# LVDS_IFC.net
KiCad netlist of a schematic drawn in Altium Designer
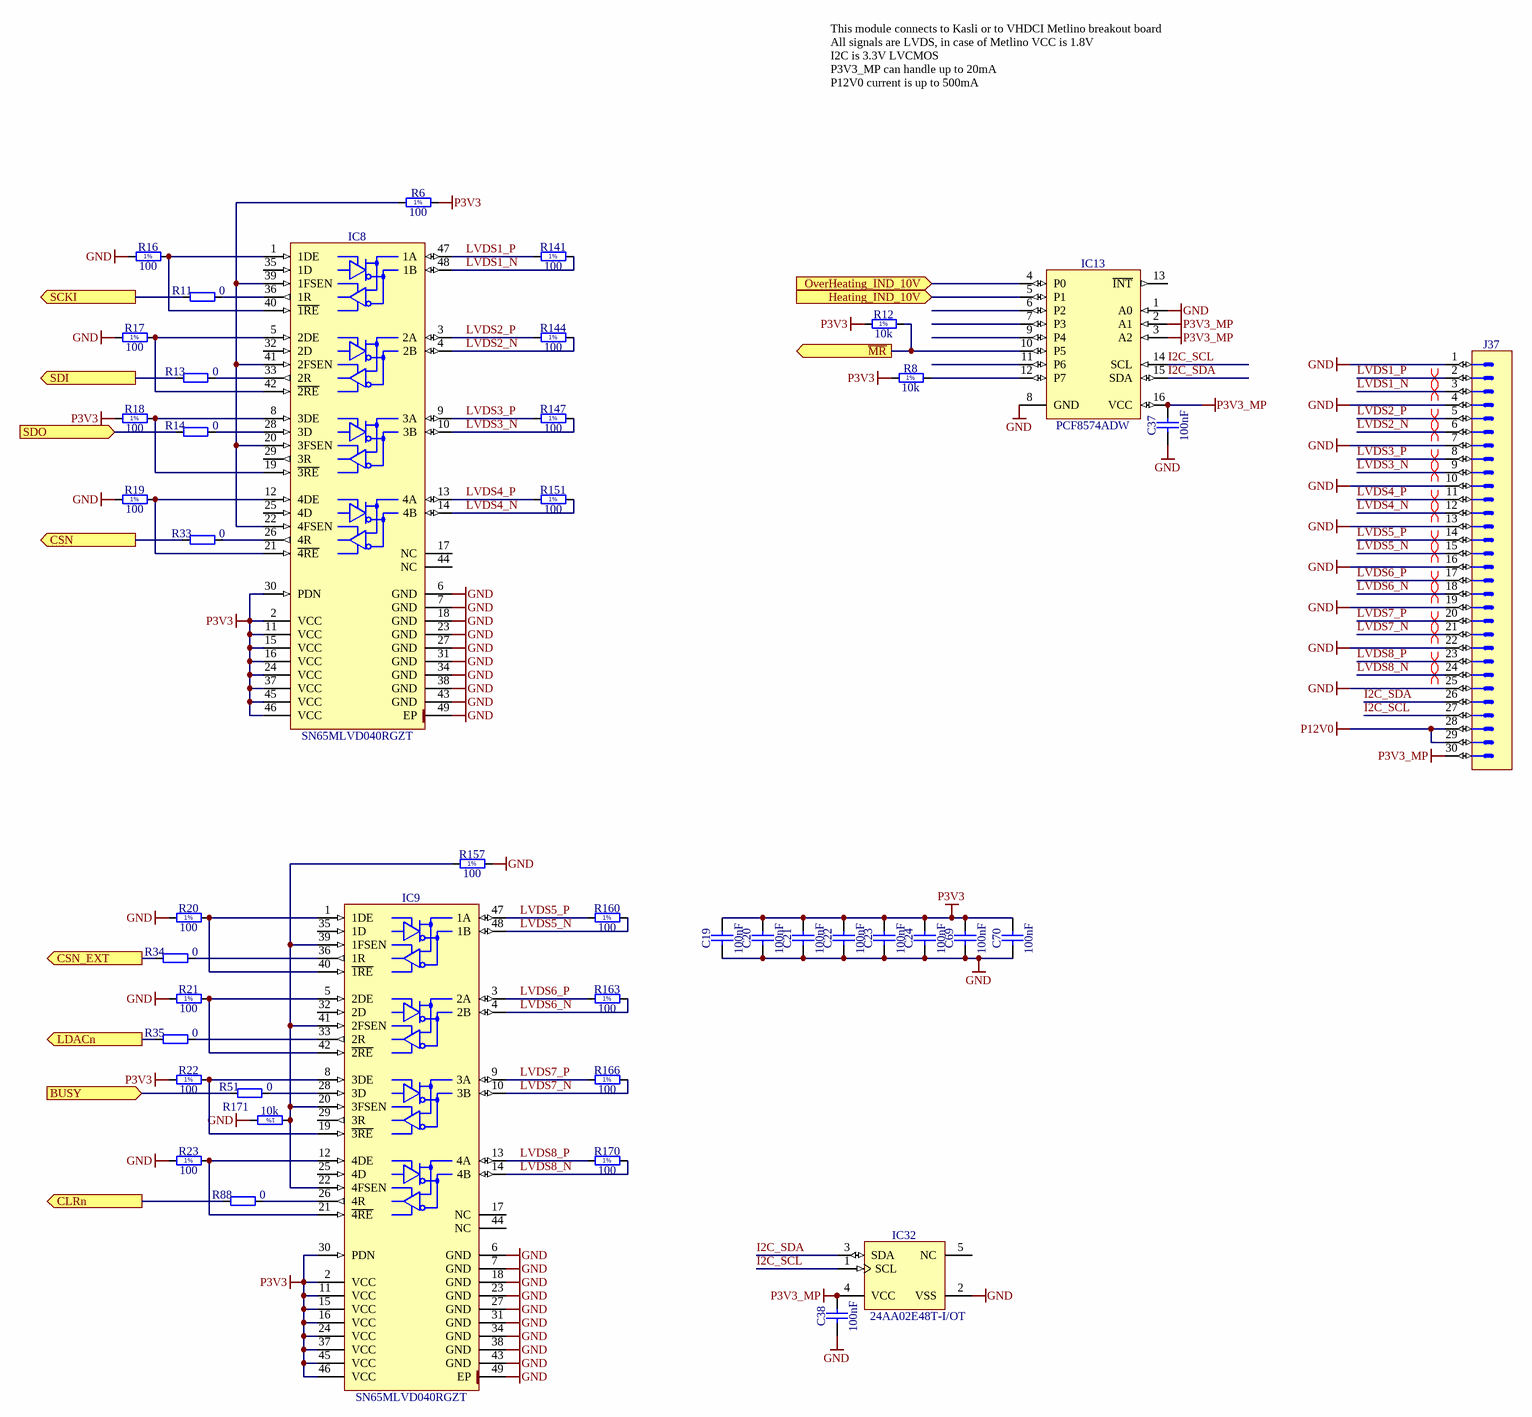
[diagram p0: LVDS_IFC.SchDoc]

(export (version "E")
  (design (tool "Eeschema 10.0.6"))
  (components
    (comp (ref "C19")
      (value "100nF")
      (footprint "CAPC1005X55N")
      (description "Non-polarised capacitor")
      (fields
        (field (name "PART NUMBER") "CC0402_100NF_16V_10%_X5R")
        (field (name "VOLTAGE") "16V")
        (field (name "AUTHOR") "CERN DEM JLC")
      )
      (libsource (lib "Capacitors") (part "Capacitor - non polarized"))
    )
    (comp (ref "C20")
      (value "100nF")
      (footprint "CAPC1005X55N")
      (description "Non-polarised capacitor")
      (fields
        (field (name "PART NUMBER") "CC0402_100NF_16V_10%_X5R")
        (field (name "VOLTAGE") "16V")
        (field (name "AUTHOR") "CERN DEM JLC")
      )
      (libsource (lib "Capacitors") (part "Capacitor - non polarized"))
    )
    (comp (ref "C21")
      (value "100nF")
      (footprint "CAPC1005X55N")
      (description "Non-polarised capacitor")
      (fields
        (field (name "PART NUMBER") "CC0402_100NF_16V_10%_X5R")
        (field (name "VOLTAGE") "16V")
        (field (name "AUTHOR") "CERN DEM JLC")
      )
      (libsource (lib "Capacitors") (part "Capacitor - non polarized"))
    )
    (comp (ref "C22")
      (value "100nF")
      (footprint "CAPC1005X55N")
      (description "Non-polarised capacitor")
      (fields
        (field (name "PART NUMBER") "CC0402_100NF_16V_10%_X5R")
        (field (name "VOLTAGE") "16V")
        (field (name "AUTHOR") "CERN DEM JLC")
      )
      (libsource (lib "Capacitors") (part "Capacitor - non polarized"))
    )
    (comp (ref "C23")
      (value "100nF")
      (footprint "CAPC1005X55N")
      (description "Non-polarised capacitor")
      (fields
        (field (name "PART NUMBER") "CC0402_100NF_16V_10%_X5R")
        (field (name "VOLTAGE") "16V")
        (field (name "AUTHOR") "CERN DEM JLC")
      )
      (libsource (lib "Capacitors") (part "Capacitor - non polarized"))
    )
    (comp (ref "C24")
      (value "100nF")
      (footprint "CAPC1005X55N")
      (description "Non-polarised capacitor")
      (fields
        (field (name "PART NUMBER") "CC0402_100NF_16V_10%_X5R")
        (field (name "VOLTAGE") "16V")
        (field (name "AUTHOR") "CERN DEM JLC")
      )
      (libsource (lib "Capacitors") (part "Capacitor - non polarized"))
    )
    (comp (ref "C37")
      (value "100nF")
      (footprint "CAPC1005X55N")
      (description "Non-polarised capacitor")
      (fields
        (field (name "PART NUMBER") "CC0402_100NF_16V_10%_X5R")
        (field (name "VOLTAGE") "16V")
        (field (name "AUTHOR") "CERN DEM JLC")
      )
      (libsource (lib "Capacitors") (part "Capacitor - non polarized"))
    )
    (comp (ref "C38")
      (value "100nF")
      (footprint "CAPC1005X55N")
      (description "Non-polarised capacitor")
      (fields
        (field (name "PART NUMBER") "CC0402_100NF_16V_10%_X5R")
        (field (name "VOLTAGE") "16V")
        (field (name "AUTHOR") "CERN DEM JLC")
      )
      (libsource (lib "Capacitors") (part "Capacitor - non polarized"))
    )
    (comp (ref "C69")
      (value "100nF")
      (footprint "CAPC1005X55N")
      (description "Non-polarised capacitor")
      (fields
        (field (name "PART NUMBER") "CC0402_100NF_16V_10%_X5R")
        (field (name "VOLTAGE") "16V")
        (field (name "AUTHOR") "CERN DEM JLC")
      )
      (libsource (lib "Capacitors") (part "Capacitor - non polarized"))
    )
    (comp (ref "C70")
      (value "100nF")
      (footprint "CAPC1005X55N")
      (description "Non-polarised capacitor")
      (fields
        (field (name "PART NUMBER") "CC0402_100NF_16V_10%_X5R")
        (field (name "VOLTAGE") "16V")
        (field (name "AUTHOR") "CERN DEM JLC")
      )
      (libsource (lib "Capacitors") (part "Capacitor - non polarized"))
    )
    (comp (ref "IC8")
      (value "SN65MLVD040RGZT")
      (footprint "QFN50P700X700X100-49N-S420")
      (description "4-Channel Half-Duplex M-LVDS Line Transceiver")
      (fields (field (name "MANUFACTURER") "TEXAS INSTRUMENTS") (field (name "AUTHOR") "CERN DEM JLC"))
      (libsource (lib "ICs And Semiconductors") (part "SN65MLVD040"))
    )
    (comp (ref "IC9")
      (value "SN65MLVD040RGZT")
      (footprint "QFN50P700X700X100-49N-S420")
      (description "4-Channel Half-Duplex M-LVDS Line Transceiver")
      (fields (field (name "MANUFACTURER") "TEXAS INSTRUMENTS") (field (name "AUTHOR") "CERN DEM JLC"))
      (libsource (lib "ICs And Semiconductors") (part "SN65MLVD040"))
    )
    (comp (ref "IC13")
      (value "PCF8574ADW")
      (footprint "SOIC127P1030X265-16N")
      (description "Remote 8-bit I/O Expander For I2C Bus")
      (fields (field (name "MANUFACTURER") "TEXAS INSTRUMENTS") (field (name "AUTHOR") "CERN DEM JLC"))
      (libsource (lib "ICs And Semiconductors") (part "PCF8574ADW"))
    )
    (comp (ref "IC32")
      (value "24AA02E48T-I/OT")
      (footprint "SOT95P280X145-5N")
      (description "1.7V-5.5V, 2K I2C Serial EEPROM With EUI-48 Node Identity")
      (fields (field (name "MANUFACTURER") "MICROCHIP TECHNOLOGY") (field (name "AUTHOR") "CERN DEM MR"))
      (libsource (lib "ICs And Semiconductors") (part "24AA02E48T-I/OT"))
    )
    (comp (ref "J37")
      (value "~")
      (footprint "3M_N2530-6002RB")
      (description "Connector 30 Male")
      (fields
        (field (name "PART NUMBER") "3M_N2530-6002RB")
        (field (name "MANUFACTURER") "3M")
        (field (name "AUTHOR") "CERN DEM JLC")
      )
      (libsource (lib "Connectors") (part "Connector 30 Male"))
    )
    (comp (ref "R6")
      (value "100")
      (footprint "RESC1005X40N")
      (description "Resistor - 1%")
      (fields
        (field (name "PART NUMBER") "R0402_100R_1%_0.1W_100PPM")
        (field (name "POWER") "0.1W")
        (field (name "AUTHOR") "CERN DEM JLC")
      )
      (libsource (lib "Resistors") (part "Resistor - 1%"))
    )
    (comp (ref "R8")
      (value "10k")
      (footprint "RESC1608X55N")
      (description "Resistor - 1%")
      (fields
        (field (name "PART NUMBER") "R0603_10K_1%_0.1W_100PPM")
        (field (name "POWER") "0.1W")
        (field (name "AUTHOR") "CERN DEM JLC")
      )
      (libsource (lib "Resistors") (part "Resistor - 1%"))
    )
    (comp (ref "R11")
      (value "0")
      (footprint "RESC1005X40N")
      (description "Resistor")
      (fields
        (field (name "PART NUMBER") "R0402_0R_JUMPER")
        (field (name "MANUFACTURER") "GENERIC")
        (field (name "AUTHOR") "CERN DEM JLC")
      )
      (libsource (lib "Resistors") (part "Resistor"))
    )
    (comp (ref "R12")
      (value "10k")
      (footprint "RESC1608X55N")
      (description "Resistor - 1%")
      (fields
        (field (name "PART NUMBER") "R0603_10K_1%_0.1W_100PPM")
        (field (name "POWER") "0.1W")
        (field (name "AUTHOR") "CERN DEM JLC")
      )
      (libsource (lib "Resistors") (part "Resistor - 1%"))
    )
    (comp (ref "R13")
      (value "0")
      (footprint "RESC1005X40N")
      (description "Resistor")
      (fields
        (field (name "PART NUMBER") "R0402_0R_JUMPER")
        (field (name "MANUFACTURER") "GENERIC")
        (field (name "AUTHOR") "CERN DEM JLC")
      )
      (libsource (lib "Resistors") (part "Resistor"))
    )
    (comp (ref "R14")
      (value "0")
      (footprint "RESC1005X40N")
      (description "Resistor")
      (fields
        (field (name "PART NUMBER") "R0402_0R_JUMPER")
        (field (name "MANUFACTURER") "GENERIC")
        (field (name "AUTHOR") "CERN DEM JLC")
      )
      (libsource (lib "Resistors") (part "Resistor"))
    )
    (comp (ref "R16")
      (value "100")
      (footprint "RESC1005X40N")
      (description "Resistor - 1%")
      (fields
        (field (name "PART NUMBER") "R0402_100R_1%_0.1W_100PPM")
        (field (name "POWER") "0.1W")
        (field (name "AUTHOR") "CERN DEM JLC")
      )
      (libsource (lib "Resistors") (part "Resistor - 1%"))
    )
    (comp (ref "R17")
      (value "100")
      (footprint "RESC1005X40N")
      (description "Resistor - 1%")
      (fields
        (field (name "PART NUMBER") "R0402_100R_1%_0.1W_100PPM")
        (field (name "POWER") "0.1W")
        (field (name "AUTHOR") "CERN DEM JLC")
      )
      (libsource (lib "Resistors") (part "Resistor - 1%"))
    )
    (comp (ref "R18")
      (value "100")
      (footprint "RESC1005X40N")
      (description "Resistor - 1%")
      (fields
        (field (name "PART NUMBER") "R0402_100R_1%_0.1W_100PPM")
        (field (name "POWER") "0.1W")
        (field (name "AUTHOR") "CERN DEM JLC")
      )
      (libsource (lib "Resistors") (part "Resistor - 1%"))
    )
    (comp (ref "R19")
      (value "100")
      (footprint "RESC1005X40N")
      (description "Resistor - 1%")
      (fields
        (field (name "PART NUMBER") "R0402_100R_1%_0.1W_100PPM")
        (field (name "POWER") "0.1W")
        (field (name "AUTHOR") "CERN DEM JLC")
      )
      (libsource (lib "Resistors") (part "Resistor - 1%"))
    )
    (comp (ref "R20")
      (value "100")
      (footprint "RESC1005X40N")
      (description "Resistor - 1%")
      (fields
        (field (name "PART NUMBER") "R0402_100R_1%_0.1W_100PPM")
        (field (name "POWER") "0.1W")
        (field (name "AUTHOR") "CERN DEM JLC")
      )
      (libsource (lib "Resistors") (part "Resistor - 1%"))
    )
    (comp (ref "R21")
      (value "100")
      (footprint "RESC1005X40N")
      (description "Resistor - 1%")
      (fields
        (field (name "PART NUMBER") "R0402_100R_1%_0.1W_100PPM")
        (field (name "POWER") "0.1W")
        (field (name "AUTHOR") "CERN DEM JLC")
      )
      (libsource (lib "Resistors") (part "Resistor - 1%"))
    )
    (comp (ref "R22")
      (value "100")
      (footprint "RESC1005X40N")
      (description "Resistor - 1%")
      (fields
        (field (name "PART NUMBER") "R0402_100R_1%_0.1W_100PPM")
        (field (name "POWER") "0.1W")
        (field (name "AUTHOR") "CERN DEM JLC")
      )
      (libsource (lib "Resistors") (part "Resistor - 1%"))
    )
    (comp (ref "R23")
      (value "100")
      (footprint "RESC1005X40N")
      (description "Resistor - 1%")
      (fields
        (field (name "PART NUMBER") "R0402_100R_1%_0.1W_100PPM")
        (field (name "POWER") "0.1W")
        (field (name "AUTHOR") "CERN DEM JLC")
      )
      (libsource (lib "Resistors") (part "Resistor - 1%"))
    )
    (comp (ref "R33")
      (value "0")
      (footprint "RESC1005X40N")
      (description "Resistor")
      (fields
        (field (name "PART NUMBER") "R0402_0R_JUMPER")
        (field (name "MANUFACTURER") "GENERIC")
        (field (name "AUTHOR") "CERN DEM JLC")
      )
      (libsource (lib "Resistors") (part "Resistor"))
    )
    (comp (ref "R34")
      (value "0")
      (footprint "RESC1005X40N")
      (description "Resistor")
      (fields
        (field (name "PART NUMBER") "R0402_0R_JUMPER")
        (field (name "MANUFACTURER") "GENERIC")
        (field (name "AUTHOR") "CERN DEM JLC")
      )
      (libsource (lib "Resistors") (part "Resistor"))
    )
    (comp (ref "R35")
      (value "0")
      (footprint "RESC1005X40N")
      (description "Resistor")
      (fields
        (field (name "PART NUMBER") "R0402_0R_JUMPER")
        (field (name "MANUFACTURER") "GENERIC")
        (field (name "AUTHOR") "CERN DEM JLC")
      )
      (libsource (lib "Resistors") (part "Resistor"))
    )
    (comp (ref "R51")
      (value "0")
      (footprint "RESC1005X40N")
      (description "Resistor")
      (fields
        (field (name "PART NUMBER") "R0402_0R_JUMPER")
        (field (name "MANUFACTURER") "GENERIC")
        (field (name "AUTHOR") "CERN DEM JLC")
      )
      (libsource (lib "Resistors") (part "Resistor"))
    )
    (comp (ref "R88")
      (value "0")
      (footprint "RESC1005X40N")
      (description "Resistor")
      (fields
        (field (name "PART NUMBER") "R0402_0R_JUMPER")
        (field (name "MANUFACTURER") "GENERIC")
        (field (name "AUTHOR") "CERN DEM JLC")
      )
      (libsource (lib "Resistors") (part "Resistor"))
    )
    (comp (ref "R141")
      (value "100")
      (footprint "RESC1005X40N")
      (description "Resistor - 1%")
      (fields
        (field (name "PART NUMBER") "R0402_100R_1%_0.1W_100PPM")
        (field (name "POWER") "0.1W")
        (field (name "AUTHOR") "CERN DEM JLC")
      )
      (libsource (lib "Resistors") (part "Resistor - 1%"))
    )
    (comp (ref "R144")
      (value "100")
      (footprint "RESC1005X40N")
      (description "Resistor - 1%")
      (fields
        (field (name "PART NUMBER") "R0402_100R_1%_0.1W_100PPM")
        (field (name "POWER") "0.1W")
        (field (name "AUTHOR") "CERN DEM JLC")
      )
      (libsource (lib "Resistors") (part "Resistor - 1%"))
    )
    (comp (ref "R147")
      (value "100")
      (footprint "RESC1005X40N")
      (description "Resistor - 1%")
      (fields
        (field (name "PART NUMBER") "R0402_100R_1%_0.1W_100PPM")
        (field (name "POWER") "0.1W")
        (field (name "AUTHOR") "CERN DEM JLC")
      )
      (libsource (lib "Resistors") (part "Resistor - 1%"))
    )
    (comp (ref "R151")
      (value "100")
      (footprint "RESC1005X40N")
      (description "Resistor - 1%")
      (fields
        (field (name "PART NUMBER") "R0402_100R_1%_0.1W_100PPM")
        (field (name "POWER") "0.1W")
        (field (name "AUTHOR") "CERN DEM JLC")
      )
      (libsource (lib "Resistors") (part "Resistor - 1%"))
    )
    (comp (ref "R157")
      (value "100")
      (footprint "RESC1005X40N")
      (description "Resistor - 1%")
      (fields
        (field (name "PART NUMBER") "R0402_100R_1%_0.1W_100PPM")
        (field (name "POWER") "0.1W")
        (field (name "AUTHOR") "CERN DEM JLC")
      )
      (libsource (lib "Resistors") (part "Resistor - 1%"))
    )
    (comp (ref "R160")
      (value "100")
      (footprint "RESC1005X40N")
      (description "Resistor - 1%")
      (fields
        (field (name "PART NUMBER") "R0402_100R_1%_0.1W_100PPM")
        (field (name "POWER") "0.1W")
        (field (name "AUTHOR") "CERN DEM JLC")
      )
      (libsource (lib "Resistors") (part "Resistor - 1%"))
    )
    (comp (ref "R163")
      (value "100")
      (footprint "RESC1005X40N")
      (description "Resistor - 1%")
      (fields
        (field (name "PART NUMBER") "R0402_100R_1%_0.1W_100PPM")
        (field (name "POWER") "0.1W")
        (field (name "AUTHOR") "CERN DEM JLC")
      )
      (libsource (lib "Resistors") (part "Resistor - 1%"))
    )
    (comp (ref "R166")
      (value "100")
      (footprint "RESC1005X40N")
      (description "Resistor - 1%")
      (fields
        (field (name "PART NUMBER") "R0402_100R_1%_0.1W_100PPM")
        (field (name "POWER") "0.1W")
        (field (name "AUTHOR") "CERN DEM JLC")
      )
      (libsource (lib "Resistors") (part "Resistor - 1%"))
    )
    (comp (ref "R170")
      (value "100")
      (footprint "RESC1005X40N")
      (description "Resistor - 1%")
      (fields
        (field (name "PART NUMBER") "R0402_100R_1%_0.1W_100PPM")
        (field (name "POWER") "0.1W")
        (field (name "AUTHOR") "CERN DEM JLC")
      )
      (libsource (lib "Resistors") (part "Resistor - 1%"))
    )
    (comp (ref "R171")
      (value "10k")
      (footprint "RESC1005X40N")
      (description "Resistor - 1%")
      (fields
        (field (name "PART NUMBER") "R0402_10K_1%_0.0625W_100PPM")
        (field (name "POWER") "0.0625W")
        (field (name "AUTHOR") "CERN DEM JLC")
      )
      (libsource (lib "Resistors") (part "Resistor - 1%"))
    )
  )
  (nets
    (net (code "1") (name "/BUSY") (class "Default")
      (node (ref "R51") (pin "1") (pinfunction "1_1") (pintype "passive"))
    )
    (net (code "2") (name "/CLRn") (class "Default")
      (node (ref "R88") (pin "1") (pinfunction "1_1") (pintype "passive"))
    )
    (net (code "3") (name "/CSN") (class "Default")
      (node (ref "R33") (pin "1") (pinfunction "1_1") (pintype "passive"))
    )
    (net (code "4") (name "/CSN_EXT") (class "Default")
      (node (ref "R34") (pin "1") (pinfunction "1_1") (pintype "passive"))
    )
    (net (code "5") (name "/Heating_IND_10V") (class "Default")
      (node (ref "IC13") (pin "5") (pinfunction "P1_5") (pintype "bidirectional"))
    )
    (net (code "6") (name "/I2C_SCL") (class "Default")
      (node (ref "IC13") (pin "14") (pinfunction "SCL_14") (pintype "input"))
      (node (ref "IC32") (pin "1") (pinfunction "SCL_1") (pintype "input"))
      (node (ref "J37") (pin "27") (pinfunction "27_27") (pintype "bidirectional"))
    )
    (net (code "7") (name "/I2C_SDA") (class "Default")
      (node (ref "IC13") (pin "15") (pinfunction "SDA_15") (pintype "bidirectional"))
      (node (ref "IC32") (pin "3") (pinfunction "SDA_3") (pintype "bidirectional"))
      (node (ref "J37") (pin "26") (pinfunction "26_26") (pintype "bidirectional"))
    )
    (net (code "8") (name "/LDACn") (class "Default")
      (node (ref "R35") (pin "1") (pinfunction "1_1") (pintype "passive"))
    )
    (net (code "9") (name "/LVDS1_N") (class "Default")
      (node (ref "IC8") (pin "48") (pinfunction "1B_48") (pintype "bidirectional"))
      (node (ref "J37") (pin "3") (pinfunction "3_3") (pintype "bidirectional"))
      (node (ref "R141") (pin "2") (pinfunction "2_2") (pintype "passive"))
    )
    (net (code "10") (name "/LVDS1_P") (class "Default")
      (node (ref "IC8") (pin "47") (pinfunction "1A_47") (pintype "bidirectional"))
      (node (ref "J37") (pin "2") (pinfunction "2_2") (pintype "bidirectional"))
      (node (ref "R141") (pin "1") (pinfunction "1_1") (pintype "passive"))
    )
    (net (code "11") (name "/LVDS2_N") (class "Default")
      (node (ref "IC8") (pin "4") (pinfunction "2B_4") (pintype "bidirectional"))
      (node (ref "J37") (pin "6") (pinfunction "6_6") (pintype "bidirectional"))
      (node (ref "R144") (pin "2") (pinfunction "2_2") (pintype "passive"))
    )
    (net (code "12") (name "/LVDS2_P") (class "Default")
      (node (ref "IC8") (pin "3") (pinfunction "2A_3") (pintype "bidirectional"))
      (node (ref "J37") (pin "5") (pinfunction "5_5") (pintype "bidirectional"))
      (node (ref "R144") (pin "1") (pinfunction "1_1") (pintype "passive"))
    )
    (net (code "13") (name "/LVDS3_N") (class "Default")
      (node (ref "IC8") (pin "10") (pinfunction "3B_10") (pintype "bidirectional"))
      (node (ref "J37") (pin "9") (pinfunction "9_9") (pintype "bidirectional"))
      (node (ref "R147") (pin "2") (pinfunction "2_2") (pintype "passive"))
    )
    (net (code "14") (name "/LVDS3_P") (class "Default")
      (node (ref "IC8") (pin "9") (pinfunction "3A_9") (pintype "bidirectional"))
      (node (ref "J37") (pin "8") (pinfunction "8_8") (pintype "bidirectional"))
      (node (ref "R147") (pin "1") (pinfunction "1_1") (pintype "passive"))
    )
    (net (code "15") (name "/LVDS4_N") (class "Default")
      (node (ref "IC8") (pin "14") (pinfunction "4B_14") (pintype "bidirectional"))
      (node (ref "J37") (pin "12") (pinfunction "12_12") (pintype "bidirectional"))
      (node (ref "R151") (pin "2") (pinfunction "2_2") (pintype "passive"))
    )
    (net (code "16") (name "/LVDS4_P") (class "Default")
      (node (ref "IC8") (pin "13") (pinfunction "4A_13") (pintype "bidirectional"))
      (node (ref "J37") (pin "11") (pinfunction "11_11") (pintype "bidirectional"))
      (node (ref "R151") (pin "1") (pinfunction "1_1") (pintype "passive"))
    )
    (net (code "17") (name "/LVDS5_N") (class "Default")
      (node (ref "IC9") (pin "48") (pinfunction "1B_48") (pintype "bidirectional"))
      (node (ref "J37") (pin "15") (pinfunction "15_15") (pintype "bidirectional"))
      (node (ref "R160") (pin "2") (pinfunction "2_2") (pintype "passive"))
    )
    (net (code "18") (name "/LVDS5_P") (class "Default")
      (node (ref "IC9") (pin "47") (pinfunction "1A_47") (pintype "bidirectional"))
      (node (ref "J37") (pin "14") (pinfunction "14_14") (pintype "bidirectional"))
      (node (ref "R160") (pin "1") (pinfunction "1_1") (pintype "passive"))
    )
    (net (code "19") (name "/LVDS6_N") (class "Default")
      (node (ref "IC9") (pin "4") (pinfunction "2B_4") (pintype "bidirectional"))
      (node (ref "J37") (pin "18") (pinfunction "18_18") (pintype "bidirectional"))
      (node (ref "R163") (pin "2") (pinfunction "2_2") (pintype "passive"))
    )
    (net (code "20") (name "/LVDS6_P") (class "Default")
      (node (ref "IC9") (pin "3") (pinfunction "2A_3") (pintype "bidirectional"))
      (node (ref "J37") (pin "17") (pinfunction "17_17") (pintype "bidirectional"))
      (node (ref "R163") (pin "1") (pinfunction "1_1") (pintype "passive"))
    )
    (net (code "21") (name "/LVDS7_N") (class "Default")
      (node (ref "IC9") (pin "10") (pinfunction "3B_10") (pintype "bidirectional"))
      (node (ref "J37") (pin "21") (pinfunction "21_21") (pintype "bidirectional"))
      (node (ref "R166") (pin "2") (pinfunction "2_2") (pintype "passive"))
    )
    (net (code "22") (name "/LVDS7_P") (class "Default")
      (node (ref "IC9") (pin "9") (pinfunction "3A_9") (pintype "bidirectional"))
      (node (ref "J37") (pin "20") (pinfunction "20_20") (pintype "bidirectional"))
      (node (ref "R166") (pin "1") (pinfunction "1_1") (pintype "passive"))
    )
    (net (code "23") (name "/LVDS8_N") (class "Default")
      (node (ref "IC9") (pin "14") (pinfunction "4B_14") (pintype "bidirectional"))
      (node (ref "J37") (pin "24") (pinfunction "24_24") (pintype "bidirectional"))
      (node (ref "R170") (pin "2") (pinfunction "2_2") (pintype "passive"))
    )
    (net (code "24") (name "/LVDS8_P") (class "Default")
      (node (ref "IC9") (pin "13") (pinfunction "4A_13") (pintype "bidirectional"))
      (node (ref "J37") (pin "23") (pinfunction "23_23") (pintype "bidirectional"))
      (node (ref "R170") (pin "1") (pinfunction "1_1") (pintype "passive"))
    )
    (net (code "25") (name "/OverHeating_IND_10V") (class "Default")
      (node (ref "IC13") (pin "4") (pinfunction "P0_4") (pintype "bidirectional"))
    )
    (net (code "26") (name "/SCKI") (class "Default")
      (node (ref "R11") (pin "1") (pinfunction "1_1") (pintype "passive"))
    )
    (net (code "27") (name "/SDI") (class "Default")
      (node (ref "R13") (pin "1") (pinfunction "1_1") (pintype "passive"))
    )
    (net (code "28") (name "/SDO") (class "Default")
      (node (ref "R14") (pin "1") (pinfunction "1_1") (pintype "passive"))
    )
    (net (code "29") (name "/~{MR}") (class "Default")
      (node (ref "IC13") (pin "10") (pinfunction "P5_10") (pintype "bidirectional"))
      (node (ref "R12") (pin "2") (pinfunction "2_2") (pintype "passive"))
    )
    (net (code "30") (name "GND") (class "Default")
      (node (ref "C19") (pin "1") (pinfunction "1_1") (pintype "passive"))
      (node (ref "C20") (pin "1") (pinfunction "1_1") (pintype "passive"))
      (node (ref "C21") (pin "1") (pinfunction "1_1") (pintype "passive"))
      (node (ref "C22") (pin "1") (pinfunction "1_1") (pintype "passive"))
      (node (ref "C23") (pin "1") (pinfunction "1_1") (pintype "passive"))
      (node (ref "C24") (pin "1") (pinfunction "1_1") (pintype "passive"))
      (node (ref "C37") (pin "1") (pinfunction "1_1") (pintype "passive"))
      (node (ref "C38") (pin "1") (pinfunction "1_1") (pintype "passive"))
      (node (ref "C69") (pin "1") (pinfunction "1_1") (pintype "passive"))
      (node (ref "C70") (pin "1") (pinfunction "1_1") (pintype "passive"))
      (node (ref "IC13") (pin "1") (pinfunction "A0_1") (pintype "input"))
      (node (ref "IC13") (pin "8") (pinfunction "GND_8") (pintype "power_in"))
      (node (ref "IC32") (pin "2") (pinfunction "VSS_2") (pintype "power_in"))
      (node (ref "IC8") (pin "18") (pinfunction "GND_18") (pintype "power_in"))
      (node (ref "IC8") (pin "23") (pinfunction "GND_23") (pintype "power_in"))
      (node (ref "IC8") (pin "27") (pinfunction "GND_27") (pintype "power_in"))
      (node (ref "IC8") (pin "31") (pinfunction "GND_31") (pintype "power_in"))
      (node (ref "IC8") (pin "34") (pinfunction "GND_34") (pintype "power_in"))
      (node (ref "IC8") (pin "38") (pinfunction "GND_38") (pintype "power_in"))
      (node (ref "IC8") (pin "43") (pinfunction "GND_43") (pintype "power_in"))
      (node (ref "IC8") (pin "49") (pinfunction "EP_49") (pintype "power_in"))
      (node (ref "IC8") (pin "6") (pinfunction "GND_6") (pintype "power_in"))
      (node (ref "IC8") (pin "7") (pinfunction "GND_7") (pintype "power_in"))
      (node (ref "IC9") (pin "18") (pinfunction "GND_18") (pintype "power_in"))
      (node (ref "IC9") (pin "23") (pinfunction "GND_23") (pintype "power_in"))
      (node (ref "IC9") (pin "27") (pinfunction "GND_27") (pintype "power_in"))
      (node (ref "IC9") (pin "31") (pinfunction "GND_31") (pintype "power_in"))
      (node (ref "IC9") (pin "34") (pinfunction "GND_34") (pintype "power_in"))
      (node (ref "IC9") (pin "38") (pinfunction "GND_38") (pintype "power_in"))
      (node (ref "IC9") (pin "43") (pinfunction "GND_43") (pintype "power_in"))
      (node (ref "IC9") (pin "49") (pinfunction "EP_49") (pintype "power_in"))
      (node (ref "IC9") (pin "6") (pinfunction "GND_6") (pintype "power_in"))
      (node (ref "IC9") (pin "7") (pinfunction "GND_7") (pintype "power_in"))
      (node (ref "J37") (pin "1") (pinfunction "1_1") (pintype "bidirectional"))
      (node (ref "J37") (pin "10") (pinfunction "10_10") (pintype "bidirectional"))
      (node (ref "J37") (pin "13") (pinfunction "13_13") (pintype "bidirectional"))
      (node (ref "J37") (pin "16") (pinfunction "16_16") (pintype "bidirectional"))
      (node (ref "J37") (pin "19") (pinfunction "19_19") (pintype "bidirectional"))
      (node (ref "J37") (pin "22") (pinfunction "22_22") (pintype "bidirectional"))
      (node (ref "J37") (pin "25") (pinfunction "25_25") (pintype "bidirectional"))
      (node (ref "J37") (pin "4") (pinfunction "4_4") (pintype "bidirectional"))
      (node (ref "J37") (pin "7") (pinfunction "7_7") (pintype "bidirectional"))
      (node (ref "R157") (pin "2") (pinfunction "2_2") (pintype "passive"))
      (node (ref "R16") (pin "1") (pinfunction "1_1") (pintype "passive"))
      (node (ref "R17") (pin "1") (pinfunction "1_1") (pintype "passive"))
      (node (ref "R171") (pin "2") (pinfunction "2_2") (pintype "passive"))
      (node (ref "R19") (pin "1") (pinfunction "1_1") (pintype "passive"))
      (node (ref "R20") (pin "1") (pinfunction "1_1") (pintype "passive"))
      (node (ref "R21") (pin "1") (pinfunction "1_1") (pintype "passive"))
      (node (ref "R23") (pin "1") (pinfunction "1_1") (pintype "passive"))
    )
    (net (code "31") (name "Net-(IC8-1DE)") (class "Default")
      (node (ref "IC8") (pin "1") (pinfunction "1DE_1") (pintype "input"))
      (node (ref "IC8") (pin "40") (pinfunction "~{1RE}_40") (pintype "input"))
      (node (ref "R16") (pin "2") (pinfunction "2_2") (pintype "passive"))
    )
    (net (code "32") (name "Net-(IC8-1FSEN)") (class "Default")
      (node (ref "IC8") (pin "20") (pinfunction "3FSEN_20") (pintype "input"))
      (node (ref "IC8") (pin "22") (pinfunction "4FSEN_22") (pintype "input"))
      (node (ref "IC8") (pin "39") (pinfunction "1FSEN_39") (pintype "input"))
      (node (ref "IC8") (pin "41") (pinfunction "2FSEN_41") (pintype "input"))
      (node (ref "R6") (pin "1") (pinfunction "1_1") (pintype "passive"))
    )
    (net (code "33") (name "Net-(IC8-1R)") (class "Default")
      (node (ref "IC8") (pin "36") (pinfunction "1R_36") (pintype "output"))
      (node (ref "R11") (pin "2") (pinfunction "2_2") (pintype "passive"))
    )
    (net (code "34") (name "Net-(IC8-2DE)") (class "Default")
      (node (ref "IC8") (pin "42") (pinfunction "~{2RE}_42") (pintype "input"))
      (node (ref "IC8") (pin "5") (pinfunction "2DE_5") (pintype "input"))
      (node (ref "R17") (pin "2") (pinfunction "2_2") (pintype "passive"))
    )
    (net (code "35") (name "Net-(IC8-2R)") (class "Default")
      (node (ref "IC8") (pin "33") (pinfunction "2R_33") (pintype "output"))
      (node (ref "R13") (pin "2") (pinfunction "2_2") (pintype "passive"))
    )
    (net (code "36") (name "Net-(IC8-3D)") (class "Default")
      (node (ref "IC8") (pin "28") (pinfunction "3D_28") (pintype "input"))
      (node (ref "R14") (pin "2") (pinfunction "2_2") (pintype "passive"))
    )
    (net (code "37") (name "Net-(IC8-3DE)") (class "Default")
      (node (ref "IC8") (pin "19") (pinfunction "~{3RE}_19") (pintype "input"))
      (node (ref "IC8") (pin "8") (pinfunction "3DE_8") (pintype "input"))
      (node (ref "R18") (pin "2") (pinfunction "2_2") (pintype "passive"))
    )
    (net (code "38") (name "Net-(IC8-4DE)") (class "Default")
      (node (ref "IC8") (pin "12") (pinfunction "4DE_12") (pintype "input"))
      (node (ref "IC8") (pin "21") (pinfunction "~{4RE}_21") (pintype "input"))
      (node (ref "R19") (pin "2") (pinfunction "2_2") (pintype "passive"))
    )
    (net (code "39") (name "Net-(IC8-4R)") (class "Default")
      (node (ref "IC8") (pin "26") (pinfunction "4R_26") (pintype "output"))
      (node (ref "R33") (pin "2") (pinfunction "2_2") (pintype "passive"))
    )
    (net (code "40") (name "Net-(IC9-1DE)") (class "Default")
      (node (ref "IC9") (pin "1") (pinfunction "1DE_1") (pintype "input"))
      (node (ref "IC9") (pin "40") (pinfunction "~{1RE}_40") (pintype "input"))
      (node (ref "R20") (pin "2") (pinfunction "2_2") (pintype "passive"))
    )
    (net (code "41") (name "Net-(IC9-1FSEN)") (class "Default")
      (node (ref "IC9") (pin "20") (pinfunction "3FSEN_20") (pintype "input"))
      (node (ref "IC9") (pin "22") (pinfunction "4FSEN_22") (pintype "input"))
      (node (ref "IC9") (pin "39") (pinfunction "1FSEN_39") (pintype "input"))
      (node (ref "IC9") (pin "41") (pinfunction "2FSEN_41") (pintype "input"))
      (node (ref "R157") (pin "1") (pinfunction "1_1") (pintype "passive"))
      (node (ref "R171") (pin "1") (pinfunction "1_1") (pintype "passive"))
    )
    (net (code "42") (name "Net-(IC9-1R)") (class "Default")
      (node (ref "IC9") (pin "36") (pinfunction "1R_36") (pintype "output"))
      (node (ref "R34") (pin "2") (pinfunction "2_2") (pintype "passive"))
    )
    (net (code "43") (name "Net-(IC9-2DE)") (class "Default")
      (node (ref "IC9") (pin "42") (pinfunction "~{2RE}_42") (pintype "input"))
      (node (ref "IC9") (pin "5") (pinfunction "2DE_5") (pintype "input"))
      (node (ref "R21") (pin "2") (pinfunction "2_2") (pintype "passive"))
    )
    (net (code "44") (name "Net-(IC9-2R)") (class "Default")
      (node (ref "IC9") (pin "33") (pinfunction "2R_33") (pintype "output"))
      (node (ref "R35") (pin "2") (pinfunction "2_2") (pintype "passive"))
    )
    (net (code "45") (name "Net-(IC9-3D)") (class "Default")
      (node (ref "IC9") (pin "28") (pinfunction "3D_28") (pintype "input"))
      (node (ref "R51") (pin "2") (pinfunction "2_2") (pintype "passive"))
    )
    (net (code "46") (name "Net-(IC9-3DE)") (class "Default")
      (node (ref "IC9") (pin "19") (pinfunction "~{3RE}_19") (pintype "input"))
      (node (ref "IC9") (pin "8") (pinfunction "3DE_8") (pintype "input"))
      (node (ref "R22") (pin "2") (pinfunction "2_2") (pintype "passive"))
    )
    (net (code "47") (name "Net-(IC9-4DE)") (class "Default")
      (node (ref "IC9") (pin "12") (pinfunction "4DE_12") (pintype "input"))
      (node (ref "IC9") (pin "21") (pinfunction "~{4RE}_21") (pintype "input"))
      (node (ref "R23") (pin "2") (pinfunction "2_2") (pintype "passive"))
    )
    (net (code "48") (name "Net-(IC9-4R)") (class "Default")
      (node (ref "IC9") (pin "26") (pinfunction "4R_26") (pintype "output"))
      (node (ref "R88") (pin "2") (pinfunction "2_2") (pintype "passive"))
    )
    (net (code "49") (name "Net-(IC13-P7)") (class "Default")
      (node (ref "IC13") (pin "12") (pinfunction "P7_12") (pintype "bidirectional"))
      (node (ref "R8") (pin "2") (pinfunction "2_2") (pintype "passive"))
    )
    (net (code "50") (name "P3V3") (class "Default")
      (node (ref "C19") (pin "2") (pinfunction "2_2") (pintype "passive"))
      (node (ref "C20") (pin "2") (pinfunction "2_2") (pintype "passive"))
      (node (ref "C21") (pin "2") (pinfunction "2_2") (pintype "passive"))
      (node (ref "C22") (pin "2") (pinfunction "2_2") (pintype "passive"))
      (node (ref "C23") (pin "2") (pinfunction "2_2") (pintype "passive"))
      (node (ref "C24") (pin "2") (pinfunction "2_2") (pintype "passive"))
      (node (ref "C69") (pin "2") (pinfunction "2_2") (pintype "passive"))
      (node (ref "C70") (pin "2") (pinfunction "2_2") (pintype "passive"))
      (node (ref "IC8") (pin "11") (pinfunction "VCC_11") (pintype "power_in"))
      (node (ref "IC8") (pin "15") (pinfunction "VCC_15") (pintype "power_in"))
      (node (ref "IC8") (pin "16") (pinfunction "VCC_16") (pintype "power_in"))
      (node (ref "IC8") (pin "2") (pinfunction "VCC_2") (pintype "power_in"))
      (node (ref "IC8") (pin "24") (pinfunction "VCC_24") (pintype "power_in"))
      (node (ref "IC8") (pin "30") (pinfunction "PDN_30") (pintype "input"))
      (node (ref "IC8") (pin "37") (pinfunction "VCC_37") (pintype "power_in"))
      (node (ref "IC8") (pin "45") (pinfunction "VCC_45") (pintype "power_in"))
      (node (ref "IC8") (pin "46") (pinfunction "VCC_46") (pintype "power_in"))
      (node (ref "IC9") (pin "11") (pinfunction "VCC_11") (pintype "power_in"))
      (node (ref "IC9") (pin "15") (pinfunction "VCC_15") (pintype "power_in"))
      (node (ref "IC9") (pin "16") (pinfunction "VCC_16") (pintype "power_in"))
      (node (ref "IC9") (pin "2") (pinfunction "VCC_2") (pintype "power_in"))
      (node (ref "IC9") (pin "24") (pinfunction "VCC_24") (pintype "power_in"))
      (node (ref "IC9") (pin "30") (pinfunction "PDN_30") (pintype "input"))
      (node (ref "IC9") (pin "37") (pinfunction "VCC_37") (pintype "power_in"))
      (node (ref "IC9") (pin "45") (pinfunction "VCC_45") (pintype "power_in"))
      (node (ref "IC9") (pin "46") (pinfunction "VCC_46") (pintype "power_in"))
      (node (ref "R12") (pin "1") (pinfunction "1_1") (pintype "passive"))
      (node (ref "R18") (pin "1") (pinfunction "1_1") (pintype "passive"))
      (node (ref "R22") (pin "1") (pinfunction "1_1") (pintype "passive"))
      (node (ref "R6") (pin "2") (pinfunction "2_2") (pintype "passive"))
      (node (ref "R8") (pin "1") (pinfunction "1_1") (pintype "passive"))
    )
    (net (code "51") (name "P3V3_MP") (class "Default")
      (node (ref "C37") (pin "2") (pinfunction "2_2") (pintype "passive"))
      (node (ref "C38") (pin "2") (pinfunction "2_2") (pintype "passive"))
      (node (ref "IC13") (pin "16") (pinfunction "VCC_16") (pintype "bidirectional"))
      (node (ref "IC13") (pin "2") (pinfunction "A1_2") (pintype "input"))
      (node (ref "IC13") (pin "3") (pinfunction "A2_3") (pintype "input"))
      (node (ref "IC32") (pin "4") (pinfunction "VCC_4") (pintype "power_in"))
      (node (ref "J37") (pin "30") (pinfunction "30_30") (pintype "bidirectional"))
    )
    (net (code "52") (name "P12V0") (class "Default")
      (node (ref "J37") (pin "28") (pinfunction "28_28") (pintype "bidirectional"))
      (node (ref "J37") (pin "29") (pinfunction "29_29") (pintype "bidirectional"))
    )
    (net (code "53") (name "unconnected-(IC8-1D-Pad35)") (class "Default")
      (node (ref "IC8") (pin "35") (pinfunction "1D_35") (pintype "input"))
    )
    (net (code "54") (name "unconnected-(IC8-2D-Pad32)") (class "Default")
      (node (ref "IC8") (pin "32") (pinfunction "2D_32") (pintype "input"))
    )
    (net (code "55") (name "unconnected-(IC8-3R-Pad29)") (class "Default")
      (node (ref "IC8") (pin "29") (pinfunction "3R_29") (pintype "output"))
    )
    (net (code "56") (name "unconnected-(IC8-4D-Pad25)") (class "Default")
      (node (ref "IC8") (pin "25") (pinfunction "4D_25") (pintype "input"))
    )
    (net (code "57") (name "unconnected-(IC8-NC-Pad17)") (class "Default")
      (node (ref "IC8") (pin "17") (pinfunction "NC_17") (pintype "passive"))
    )
    (net (code "58") (name "unconnected-(IC8-NC-Pad44)") (class "Default")
      (node (ref "IC8") (pin "44") (pinfunction "NC_44") (pintype "passive"))
    )
    (net (code "59") (name "unconnected-(IC9-1D-Pad35)") (class "Default")
      (node (ref "IC9") (pin "35") (pinfunction "1D_35") (pintype "input"))
    )
    (net (code "60") (name "unconnected-(IC9-2D-Pad32)") (class "Default")
      (node (ref "IC9") (pin "32") (pinfunction "2D_32") (pintype "input"))
    )
    (net (code "61") (name "unconnected-(IC9-3R-Pad29)") (class "Default")
      (node (ref "IC9") (pin "29") (pinfunction "3R_29") (pintype "output"))
    )
    (net (code "62") (name "unconnected-(IC9-4D-Pad25)") (class "Default")
      (node (ref "IC9") (pin "25") (pinfunction "4D_25") (pintype "input"))
    )
    (net (code "63") (name "unconnected-(IC9-NC-Pad17)") (class "Default")
      (node (ref "IC9") (pin "17") (pinfunction "NC_17") (pintype "passive"))
    )
    (net (code "64") (name "unconnected-(IC9-NC-Pad44)") (class "Default")
      (node (ref "IC9") (pin "44") (pinfunction "NC_44") (pintype "passive"))
    )
    (net (code "65") (name "unconnected-(IC13-P2-Pad6)") (class "Default")
      (node (ref "IC13") (pin "6") (pinfunction "P2_6") (pintype "bidirectional"))
    )
    (net (code "66") (name "unconnected-(IC13-P3-Pad7)") (class "Default")
      (node (ref "IC13") (pin "7") (pinfunction "P3_7") (pintype "bidirectional"))
    )
    (net (code "67") (name "unconnected-(IC13-P4-Pad9)") (class "Default")
      (node (ref "IC13") (pin "9") (pinfunction "P4_9") (pintype "bidirectional"))
    )
    (net (code "68") (name "unconnected-(IC13-P6-Pad11)") (class "Default")
      (node (ref "IC13") (pin "11") (pinfunction "P6_11") (pintype "bidirectional"))
    )
    (net (code "69") (name "unconnected-(IC13-~{INT}-Pad13)") (class "Default")
      (node (ref "IC13") (pin "13") (pinfunction "~{INT}_13") (pintype "output"))
    )
    (net (code "70") (name "unconnected-(IC32-NC-Pad5)") (class "Default")
      (node (ref "IC32") (pin "5") (pinfunction "NC_5") (pintype "passive"))
    )
  )
)
